# Aux_Power.net
KiCad netlist of a schematic drawn in Altium Designer
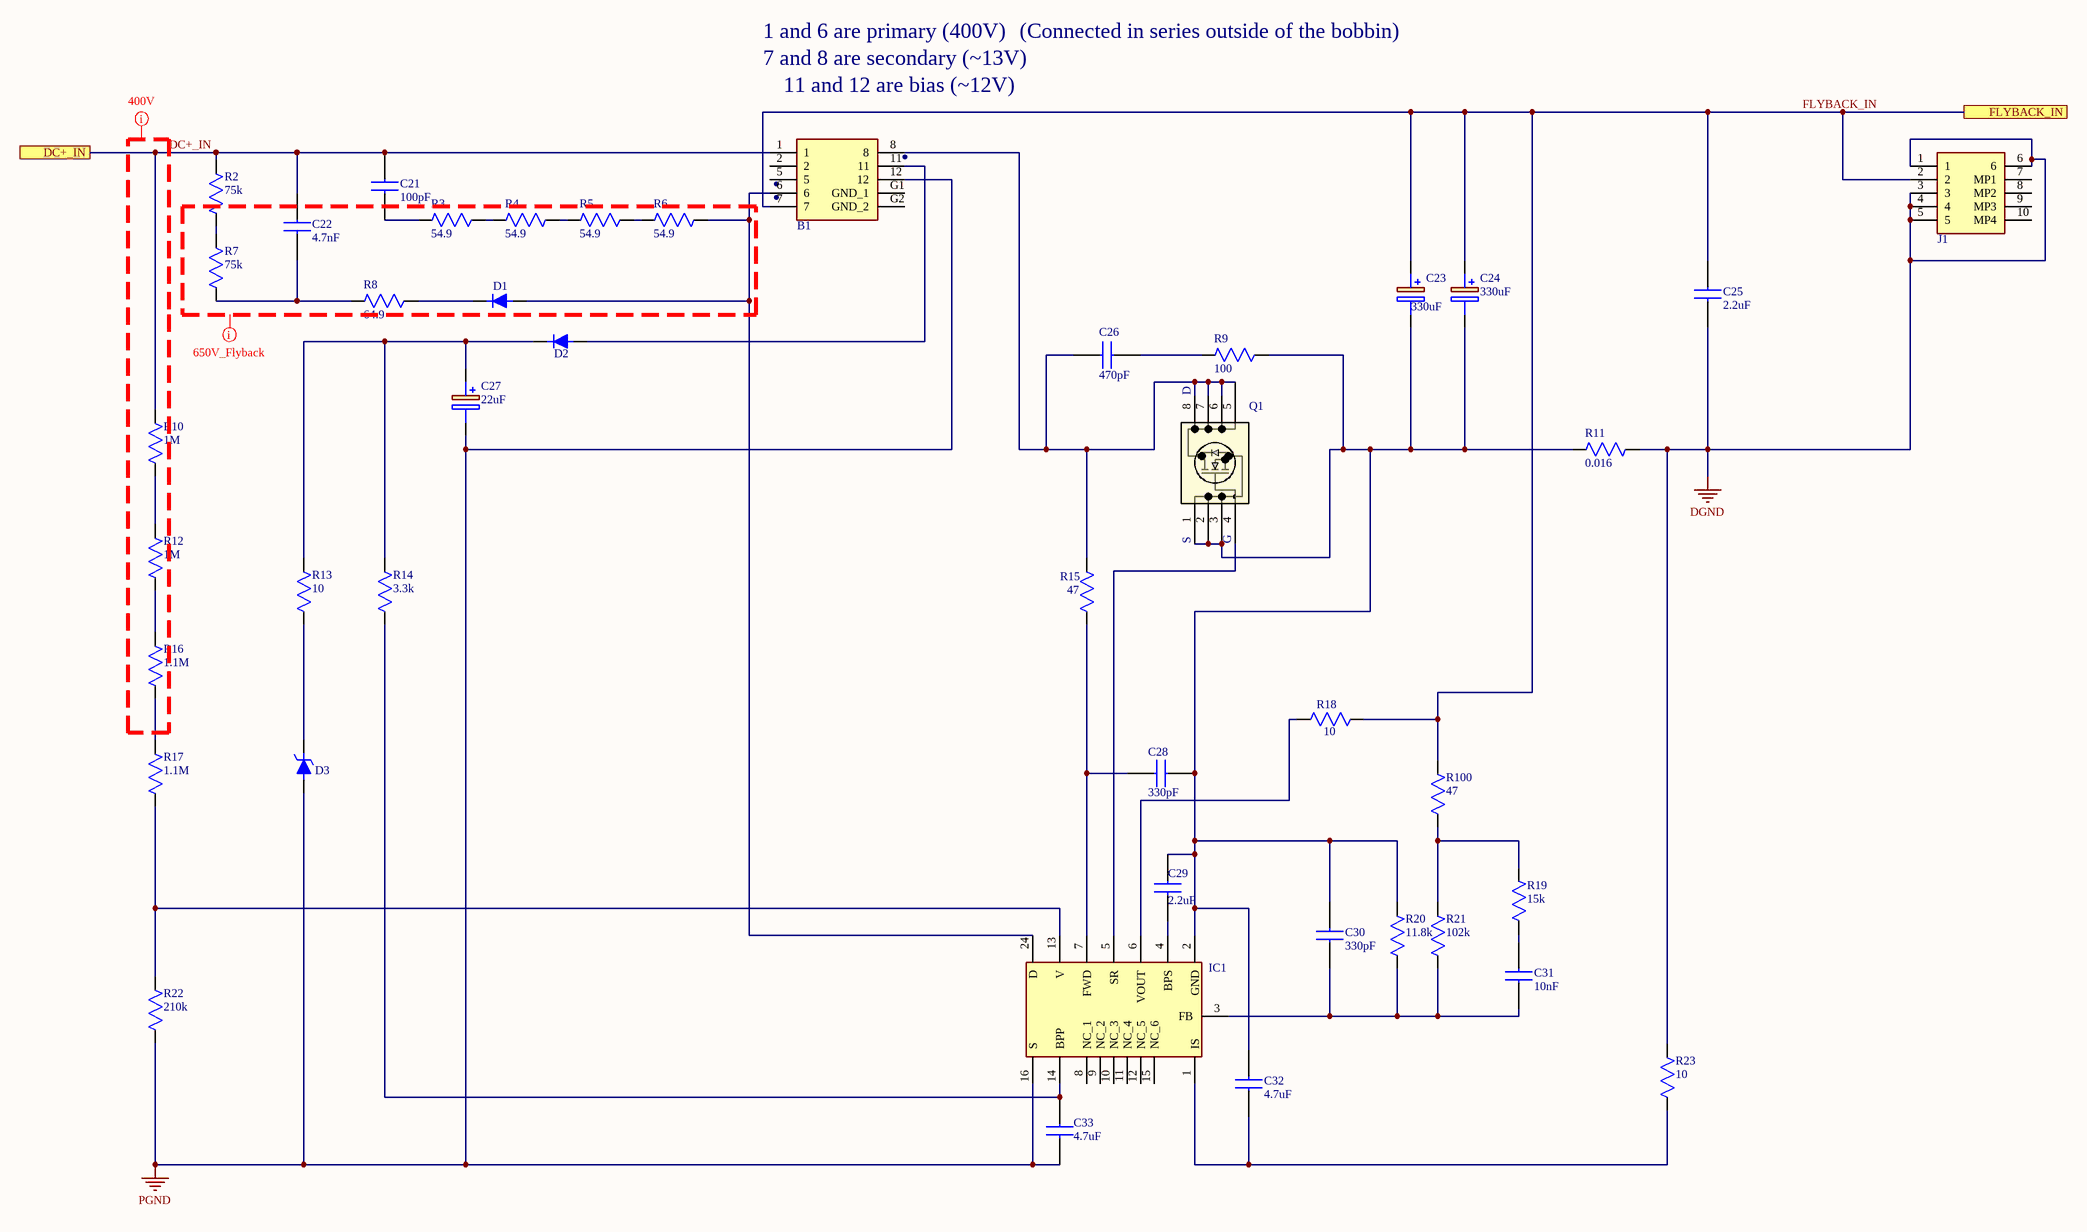
[diagram p0: Aux_Power.SchDoc]

(export (version "E")
  (design (tool "Eeschema 10.0.6"))
  (components
    (comp (ref "B1")
      (value "B65812N1008D001")
      (footprint "B65812N1008D001 - duplicate")
      (description "BOBBIN COIL FORMER RM 8")
      (fields (field (name "MOUSER PART NUMBER") "871-B65812N1008D001"))
      (libsource (lib "AuxPower") (part "B65812N1008D001"))
    )
    (comp (ref "C21")
      (value "100pF")
      (footprint "Cap 0805")
      (description "CAP CER 100PF 1000V X7R 0805")
      (libsource (lib "AuxPower") (part "885342207015"))
    )
    (comp (ref "C22")
      (value "4.7nF")
      (footprint "Cap 0805")
      (description "CAP CER 4700PF 450V C0G 0805")
      (libsource (lib "AuxPower") (part "C2012C0G2W472J125AA"))
    )
    (comp (ref "C23")
      (value "330uF")
      (footprint "CAPPC6465X560N")
      (description "CAP TANT 330UF 20% 20V 3226")
      (libsource (lib "AuxPower") (part "597D337X0020H2T"))
    )
    (comp (ref "C24")
      (value "330uF")
      (footprint "CAPPC6465X560N")
      (description "CAP TANT 330UF 20% 20V 3226")
      (libsource (lib "AuxPower") (part "597D337X0020H2T"))
    )
    (comp (ref "C25")
      (value "2.2uF")
      (footprint "Cap 0805")
      (description "2.2 µF ±10% 25V Ceramic Capacitor X7R 0805 (2012 Metric)")
      (libsource (lib "AuxPower") (part "CL21B225KAFNFNE"))
    )
    (comp (ref "C26")
      (value "470pF")
      (footprint "Cap 0805")
      (description "CAP CER 470PF 100V X7R 0805")
      (libsource (lib "AuxPower") (part "885012207114"))
    )
    (comp (ref "C27")
      (value "22uF")
      (footprint "CAP_195D_R_VIS")
      (description "CAP TANT 22UF 10% 35V 2824")
      (libsource (lib "AuxPower") (part "195D226X9035R2T"))
    )
    (comp (ref "C28")
      (value "330pF")
      (footprint "Cap 0805")
      (description "330 pF ±5% 250V Ceramic Capacitor C0G, NP0 0805 (2012 Metric)")
      (libsource (lib "AuxPower") (part "GCM21A5C2E331JX01D"))
    )
    (comp (ref "C29")
      (value "2.2uF")
      (footprint "Cap 0805")
      (description "2.2 µF ±10% 25V Ceramic Capacitor X7R 0805 (2012 Metric)")
      (libsource (lib "AuxPower") (part "CL21B225KAFNFNE"))
    )
    (comp (ref "C30")
      (value "330pF")
      (footprint "Cap 0805")
      (description "330 pF ±10% 50V Ceramic Capacitor X7R 0805 (2012 Metric)")
      (libsource (lib "AuxPower") (part "CC0805KRX7R9BB331"))
    )
    (comp (ref "C31")
      (value "10nF")
      (footprint "Cap 0805")
      (description "CAP CER 10000PF 25V X7R 0805")
      (libsource (lib "AuxPower") (part "CC0805KRX7R8BB103"))
    )
    (comp (ref "C32")
      (value "4.7uF")
      (footprint "Cap 0805")
      (description "4.7 µF ±10% 10V Ceramic Capacitor X7R 0805 (2012 Metric)")
      (libsource (lib "AuxPower") (part "LMK212B7475KGHT"))
    )
    (comp (ref "C33")
      (value "4.7uF")
      (footprint "Cap 0805")
      (description "4.7 µF ±10% 16V Ceramic Capacitor X7R 0805 (2012 Metric)")
      (libsource (lib "AuxPower") (part "CL21B475KOFNNNE"))
    )
    (comp (ref "D1")
      (value "637-S2T")
      (footprint "DO-214AA_SMB")
      (description "Diotec Semiconductor              Rectifiers Diode, SMB, 1300V, 2A")
      (fields
        (field (name "MANUFACTURER_PART_NUMBER") "UFM13PL-TP")
        (field (name "MOUSER PART NUMBER") "833-UFM13PL-TP")
      )
      (libsource (lib "AuxPower") (part "637-S2T"))
    )
    (comp (ref "D2")
      (value "BAV21WS-7-F")
      (footprint "SOD2513X120N")
      (description "DIODE STANDARD 200V 200MA SOD323")
      (fields
        (field (name "MANUFACTURER_PART_NUMBER") "UFM13PL-TP")
        (field (name "MOUSER PART NUMBER") "833-UFM13PL-TP")
      )
      (libsource (lib "AuxPower") (part "BAV21WS-7-F"))
    )
    (comp (ref "D3")
      (value "MMSZ5247BT1G")
      (footprint "SOD3716X135N")
      (description "Zener Diode 17 V 500 mW ±5% Surface Mount SOD-123")
      (fields
        (field (name "MANUFACTURER_PART_NUMBER") "UFM13PL-TP")
        (field (name "MOUSER PART NUMBER") "833-UFM13PL-TP")
      )
      (libsource (lib "AuxPower") (part "MMSZ5247BT1G"))
    )
    (comp (ref "IC1")
      (value "Flyback converter IC")
      (footprint "INN3694CH606TL")
      (description "Converter Offline Flyback, Secondary Side SR Topology 100kHz InSOP-24D")
      (fields
        (field (name "MANUFACTURER_PART_NUMBER") "INN3694C-H606-TL")
        (field (name "MOUSER PART NUMBER") "869-INN3694C-H606-TL")
      )
      (libsource (lib "AuxPower") (part "INN3694C-H606-TL"))
    )
    (comp (ref "J1")
      (value "0527450696")
      (footprint "0527450696")
      (description "CONN FFC FPC TOP 6POS 0.5MM R/A")
      (libsource (lib "AuxPower") (part "0527450696"))
    )
    (comp (ref "Q1")
      (value "AON6250")
      (footprint "AON6250")
      (description "MOSFET N-CH 150V 13.5A/52A 8DFN")
      (libsource (lib "AuxPower") (part "AON6250"))
    )
    (comp (ref "R2")
      (value "75k")
      (footprint "Resistor 0805")
      (description "RES 75K OHM 1% 1/8W 0805")
      (libsource (lib "AuxPower") (part "RMCF0805FT75K0"))
    )
    (comp (ref "R3")
      (value "54.9")
      (footprint "RESISTOR 1210")
      (description "RES 54.9 OHM 1% 1/2W 1210")
      (libsource (lib "AuxPower") (part "RMCF1210FT54R9"))
    )
    (comp (ref "R4")
      (value "54.9")
      (footprint "RESISTOR 1210")
      (description "RES 54.9 OHM 1% 1/2W 1210")
      (libsource (lib "AuxPower") (part "RMCF1210FT54R9"))
    )
    (comp (ref "R5")
      (value "54.9")
      (footprint "RESISTOR 1210")
      (description "RES 54.9 OHM 1% 1/2W 1210")
      (libsource (lib "AuxPower") (part "RMCF1210FT54R9"))
    )
    (comp (ref "R6")
      (value "54.9")
      (footprint "RESISTOR 1210")
      (description "RES 54.9 OHM 1% 1/2W 1210")
      (libsource (lib "AuxPower") (part "RMCF1210FT54R9"))
    )
    (comp (ref "R7")
      (value "75k")
      (footprint "Resistor 0805")
      (description "RES 75K OHM 1% 1/8W 0805")
      (libsource (lib "AuxPower") (part "RMCF0805FT75K0"))
    )
    (comp (ref "R8")
      (value "64.9")
      (footprint "RESISTOR 2512")
      (description "RES 64.9 OHM 1% 1W 2512")
      (libsource (lib "AuxPower") (part "RMCF2512FT64R9"))
    )
    (comp (ref "R9")
      (value "100")
      (footprint "Resistor 1206")
      (description "RES 100 OHM 1% 1/4W 1206")
      (libsource (lib "AuxPower") (part "RMCF1206FG100R"))
    )
    (comp (ref "R10")
      (value "1M")
      (footprint "Resistor 0805")
      (description "RES SMD 1M OHM 0.1% 1/8W 0805")
      (libsource (lib "AuxPower") (part "RG2012P-105-B-T5"))
    )
    (comp (ref "R11")
      (value "0.016")
      (footprint "Resistor 1206")
      (description "RES 0.016 OHM 1% 1/4W 1206")
      (libsource (lib "AuxPower") (part "RL1206FR-070R016L"))
    )
    (comp (ref "R12")
      (value "1M")
      (footprint "Resistor 0805")
      (description "RES SMD 1M OHM 0.1% 1/8W 0805")
      (libsource (lib "AuxPower") (part "RG2012P-105-B-T5"))
    )
    (comp (ref "R13")
      (value "10")
      (footprint "Resistor 0805")
      (description "RES 10 OHM 1% 1/10W 0805")
      (libsource (lib "AuxPower") (part "CR0805-10W-10R0FT"))
    )
    (comp (ref "R14")
      (value "3.3k")
      (footprint "Resistor 0805")
      (description "RES 3.3K OHM 1% 1/8W 0805")
      (libsource (lib "AuxPower") (part "RMCF0805FT3K30"))
    )
    (comp (ref "R15")
      (value "47")
      (footprint "Resistor 0805")
      (description "RES 47 OHM 1% 1/4W 0805")
      (libsource (lib "AuxPower") (part "RK73H2ATTD47R0F"))
    )
    (comp (ref "R16")
      (value "1.1M")
      (footprint "Resistor 0805")
      (description "RES SMD 1.1M OHM 0.1% 1/10W 0805")
      (libsource (lib "AuxPower") (part "CPF0805B1M1E1"))
    )
    (comp (ref "R17")
      (value "1.1M")
      (footprint "Resistor 0805")
      (description "RES SMD 1.1M OHM 0.1% 1/10W 0805")
      (libsource (lib "AuxPower") (part "CPF0805B1M1E1"))
    )
    (comp (ref "R18")
      (value "10")
      (footprint "Resistor 0805")
      (description "RES 10 OHM 1% 1/10W 0805")
      (libsource (lib "AuxPower") (part "CR0805-10W-10R0FT"))
    )
    (comp (ref "R19")
      (value "15k")
      (footprint "Resistor 0805")
      (description "CHIP RESISTOR,0805,1/10W, 15K,1%")
      (libsource (lib "AuxPower") (part "CR0805-10W-1502FT-CT"))
    )
    (comp (ref "R20")
      (value "11.8k")
      (footprint "Resistor 0603")
      (description "RES SMD 11.8K OHM 1% 1/10W 0603")
      (libsource (lib "AuxPower") (part "ERJ-3EKF1182V"))
    )
    (comp (ref "R21")
      (value "102k")
      (footprint "Resistor 0603")
      (description "RES SMD 102K OHM 1% 1/10W 0603")
      (libsource (lib "AuxPower") (part "ERJ-3EKF1023V"))
    )
    (comp (ref "R22")
      (value "210k")
      (footprint "Resistor 0805")
      (description "RES SMD 210K OHM 0.1% 1/8W 0805")
      (libsource (lib "AuxPower") (part "ERA-6AEB2103V"))
    )
    (comp (ref "R23")
      (value "10")
      (footprint "Resistor 0805")
      (description "RES SMD 10 OHM 1% 1/8W 0805")
      (libsource (lib "AuxPower") (part "ERJ-6ENF10R0V"))
    )
    (comp (ref "R100")
      (value "47")
      (footprint "Resistor 0805")
      (description "RES 47 OHM 1% 1/4W 0805")
      (libsource (lib "AuxPower") (part "RK73H2ATTD47R0F"))
    )
  )
  (nets
    (net (code "1") (name "/DC+_IN") (class "Default")
      (node (ref "B1") (pin "1") (pinfunction "1_1") (pintype "passive"))
      (node (ref "C21") (pin "2") (pinfunction "2_2") (pintype "passive"))
      (node (ref "C22") (pin "2") (pinfunction "2_2") (pintype "passive"))
      (node (ref "R10") (pin "2") (pinfunction "2_2") (pintype "passive"))
      (node (ref "R2") (pin "2") (pinfunction "2_2") (pintype "passive"))
    )
    (net (code "2") (name "/FLYBACK_IN") (class "Default")
      (node (ref "B1") (pin "7") (pinfunction "7_7") (pintype "passive"))
      (node (ref "C23") (pin "1") (pinfunction "+_1") (pintype "passive"))
      (node (ref "C24") (pin "1") (pinfunction "+_1") (pintype "passive"))
      (node (ref "C25") (pin "2") (pinfunction "2_2") (pintype "passive"))
      (node (ref "J1") (pin "2") (pinfunction "2_2") (pintype "passive"))
      (node (ref "R100") (pin "2") (pinfunction "2_2") (pintype "passive"))
      (node (ref "R18") (pin "1") (pinfunction "1_1") (pintype "passive"))
    )
    (net (code "3") (name "DGND") (class "Default")
      (node (ref "C25") (pin "1") (pinfunction "1_1") (pintype "passive"))
      (node (ref "J1") (pin "1") (pinfunction "1_1") (pintype "passive"))
      (node (ref "J1") (pin "3") (pinfunction "3_3") (pintype "passive"))
      (node (ref "J1") (pin "4") (pinfunction "4_4") (pintype "passive"))
      (node (ref "J1") (pin "5") (pinfunction "5_5") (pintype "passive"))
      (node (ref "J1") (pin "6") (pinfunction "6_6") (pintype "passive"))
      (node (ref "R11") (pin "2") (pinfunction "2_2") (pintype "passive"))
      (node (ref "R23") (pin "2") (pinfunction "2_2") (pintype "passive"))
    )
    (net (code "4") (name "Net-(B1-Pad8)") (class "Default")
      (node (ref "B1") (pin "8") (pinfunction "8_8") (pintype "passive"))
      (node (ref "C26") (pin "1") (pinfunction "1_1") (pintype "passive"))
      (node (ref "Q1") (pin "5") (pinfunction "5_5") (pintype "passive"))
      (node (ref "Q1") (pin "6") (pinfunction "6_6") (pintype "passive"))
      (node (ref "Q1") (pin "7") (pinfunction "7_7") (pintype "passive"))
      (node (ref "Q1") (pin "8") (pinfunction "8_8") (pintype "passive"))
      (node (ref "R15") (pin "2") (pinfunction "2_2") (pintype "passive"))
    )
    (net (code "5") (name "Net-(B1-Pad11)") (class "Default")
      (node (ref "B1") (pin "11") (pinfunction "11_11") (pintype "passive"))
      (node (ref "D2") (pin "1") (pinfunction "1_1") (pintype "passive"))
    )
    (net (code "6") (name "Net-(C21-Pad1)") (class "Default")
      (node (ref "C21") (pin "1") (pinfunction "1_1") (pintype "passive"))
      (node (ref "R3") (pin "1") (pinfunction "1_1") (pintype "passive"))
    )
    (net (code "7") (name "Net-(C22-Pad1)") (class "Default")
      (node (ref "C22") (pin "1") (pinfunction "1_1") (pintype "passive"))
      (node (ref "R7") (pin "1") (pinfunction "1_1") (pintype "passive"))
      (node (ref "R8") (pin "1") (pinfunction "1_1") (pintype "passive"))
    )
    (net (code "8") (name "Net-(C23--)") (class "Default")
      (node (ref "C23") (pin "2") (pinfunction "-_2") (pintype "passive"))
      (node (ref "C24") (pin "2") (pinfunction "-_2") (pintype "passive"))
      (node (ref "C28") (pin "2") (pinfunction "2_2") (pintype "passive"))
      (node (ref "C29") (pin "2") (pinfunction "2_2") (pintype "passive"))
      (node (ref "C30") (pin "1") (pinfunction "1_1") (pintype "passive"))
      (node (ref "C32") (pin "1") (pinfunction "1_1") (pintype "passive"))
      (node (ref "IC1") (pin "2") (pinfunction "GND_2") (pintype "passive"))
      (node (ref "Q1") (pin "1") (pinfunction "1_1") (pintype "passive"))
      (node (ref "Q1") (pin "2") (pinfunction "2_2") (pintype "passive"))
      (node (ref "Q1") (pin "3") (pinfunction "3_3") (pintype "passive"))
      (node (ref "R11") (pin "1") (pinfunction "1_1") (pintype "passive"))
      (node (ref "R20") (pin "2") (pinfunction "2_2") (pintype "passive"))
      (node (ref "R9") (pin "2") (pinfunction "2_2") (pintype "passive"))
    )
    (net (code "9") (name "Net-(C26-Pad2)") (class "Default")
      (node (ref "C26") (pin "2") (pinfunction "2_2") (pintype "passive"))
      (node (ref "R9") (pin "1") (pinfunction "1_1") (pintype "passive"))
    )
    (net (code "10") (name "Net-(C27-+)") (class "Default")
      (node (ref "C27") (pin "1") (pinfunction "+_1") (pintype "passive"))
      (node (ref "D2") (pin "2") (pinfunction "2_2") (pintype "passive"))
      (node (ref "R13") (pin "2") (pinfunction "2_2") (pintype "passive"))
      (node (ref "R14") (pin "2") (pinfunction "2_2") (pintype "passive"))
    )
    (net (code "11") (name "Net-(C31-Pad1)") (class "Default")
      (node (ref "C31") (pin "1") (pinfunction "1_1") (pintype "passive"))
      (node (ref "R19") (pin "2") (pinfunction "2_2") (pintype "passive"))
    )
    (net (code "12") (name "Net-(D1-Pad2)") (class "Default")
      (node (ref "D1") (pin "2") (pinfunction "2_2") (pintype "passive"))
      (node (ref "R8") (pin "2") (pinfunction "2_2") (pintype "passive"))
    )
    (net (code "13") (name "Net-(D3-Pad2)") (class "Default")
      (node (ref "D3") (pin "2") (pinfunction "2_2") (pintype "passive"))
      (node (ref "R13") (pin "1") (pinfunction "1_1") (pintype "passive"))
    )
    (net (code "14") (name "Net-(IC1-BPP)") (class "Default")
      (node (ref "C33") (pin "2") (pinfunction "2_2") (pintype "passive"))
      (node (ref "IC1") (pin "14") (pinfunction "BPP_14") (pintype "passive"))
      (node (ref "R14") (pin "1") (pinfunction "1_1") (pintype "passive"))
    )
    (net (code "15") (name "Net-(IC1-BPS)") (class "Default")
      (node (ref "C29") (pin "1") (pinfunction "1_1") (pintype "passive"))
      (node (ref "IC1") (pin "4") (pinfunction "BPS_4") (pintype "passive"))
    )
    (net (code "16") (name "Net-(IC1-D)") (class "Default")
      (node (ref "B1") (pin "6") (pinfunction "6_6") (pintype "passive"))
      (node (ref "D1") (pin "1") (pinfunction "1_1") (pintype "passive"))
      (node (ref "IC1") (pin "24") (pinfunction "D_24") (pintype "passive"))
      (node (ref "R6") (pin "2") (pinfunction "2_2") (pintype "passive"))
    )
    (net (code "17") (name "Net-(IC1-FB)") (class "Default")
      (node (ref "C30") (pin "2") (pinfunction "2_2") (pintype "passive"))
      (node (ref "C31") (pin "2") (pinfunction "2_2") (pintype "passive"))
      (node (ref "IC1") (pin "3") (pinfunction "FB_3") (pintype "passive"))
      (node (ref "R20") (pin "1") (pinfunction "1_1") (pintype "passive"))
      (node (ref "R21") (pin "1") (pinfunction "1_1") (pintype "passive"))
    )
    (net (code "18") (name "Net-(IC1-FWD)") (class "Default")
      (node (ref "C28") (pin "1") (pinfunction "1_1") (pintype "passive"))
      (node (ref "IC1") (pin "7") (pinfunction "FWD_7") (pintype "passive"))
      (node (ref "R15") (pin "1") (pinfunction "1_1") (pintype "passive"))
    )
    (net (code "19") (name "Net-(IC1-IS)") (class "Default")
      (node (ref "C32") (pin "2") (pinfunction "2_2") (pintype "passive"))
      (node (ref "IC1") (pin "1") (pinfunction "IS_1") (pintype "passive"))
      (node (ref "R23") (pin "1") (pinfunction "1_1") (pintype "passive"))
    )
    (net (code "20") (name "Net-(IC1-SR)") (class "Default")
      (node (ref "IC1") (pin "5") (pinfunction "SR_5") (pintype "passive"))
      (node (ref "Q1") (pin "4") (pinfunction "4_4") (pintype "passive"))
    )
    (net (code "21") (name "Net-(IC1-V)") (class "Default")
      (node (ref "IC1") (pin "13") (pinfunction "V_13") (pintype "passive"))
      (node (ref "R17") (pin "1") (pinfunction "1_1") (pintype "passive"))
      (node (ref "R22") (pin "2") (pinfunction "2_2") (pintype "passive"))
    )
    (net (code "22") (name "Net-(IC1-VOUT)") (class "Default")
      (node (ref "IC1") (pin "6") (pinfunction "VOUT_6") (pintype "passive"))
      (node (ref "R18") (pin "2") (pinfunction "2_2") (pintype "passive"))
    )
    (net (code "23") (name "Net-(R2-Pad1)") (class "Default")
      (node (ref "R2") (pin "1") (pinfunction "1_1") (pintype "passive"))
      (node (ref "R7") (pin "2") (pinfunction "2_2") (pintype "passive"))
    )
    (net (code "24") (name "Net-(R3-Pad2)") (class "Default")
      (node (ref "R3") (pin "2") (pinfunction "2_2") (pintype "passive"))
      (node (ref "R4") (pin "1") (pinfunction "1_1") (pintype "passive"))
    )
    (net (code "25") (name "Net-(R4-Pad2)") (class "Default")
      (node (ref "R4") (pin "2") (pinfunction "2_2") (pintype "passive"))
      (node (ref "R5") (pin "1") (pinfunction "1_1") (pintype "passive"))
    )
    (net (code "26") (name "Net-(R5-Pad2)") (class "Default")
      (node (ref "R5") (pin "2") (pinfunction "2_2") (pintype "passive"))
      (node (ref "R6") (pin "1") (pinfunction "1_1") (pintype "passive"))
    )
    (net (code "27") (name "Net-(R10-Pad1)") (class "Default")
      (node (ref "R10") (pin "1") (pinfunction "1_1") (pintype "passive"))
      (node (ref "R12") (pin "2") (pinfunction "2_2") (pintype "passive"))
    )
    (net (code "28") (name "Net-(R12-Pad1)") (class "Default")
      (node (ref "R12") (pin "1") (pinfunction "1_1") (pintype "passive"))
      (node (ref "R16") (pin "2") (pinfunction "2_2") (pintype "passive"))
    )
    (net (code "29") (name "Net-(R16-Pad1)") (class "Default")
      (node (ref "R16") (pin "1") (pinfunction "1_1") (pintype "passive"))
      (node (ref "R17") (pin "2") (pinfunction "2_2") (pintype "passive"))
    )
    (net (code "30") (name "Net-(R100-Pad1)") (class "Default")
      (node (ref "R100") (pin "1") (pinfunction "1_1") (pintype "passive"))
      (node (ref "R19") (pin "1") (pinfunction "1_1") (pintype "passive"))
      (node (ref "R21") (pin "2") (pinfunction "2_2") (pintype "passive"))
    )
    (net (code "31") (name "PGND") (class "Default")
      (node (ref "B1") (pin "12") (pinfunction "12_12") (pintype "passive"))
      (node (ref "C27") (pin "2") (pinfunction "-_2") (pintype "passive"))
      (node (ref "C33") (pin "1") (pinfunction "1_1") (pintype "passive"))
      (node (ref "D3") (pin "1") (pinfunction "1_1") (pintype "passive"))
      (node (ref "IC1") (pin "16") (pinfunction "S_16") (pintype "passive"))
      (node (ref "R22") (pin "1") (pinfunction "1_1") (pintype "passive"))
    )
    (net (code "32") (name "unconnected-(B1-GND_1-PadG1)") (class "Default")
      (node (ref "B1") (pin "G1") (pinfunction "GND_1_G1") (pintype "passive"))
    )
    (net (code "33") (name "unconnected-(B1-GND_2-PadG2)") (class "Default")
      (node (ref "B1") (pin "G2") (pinfunction "GND_2_G2") (pintype "passive"))
    )
    (net (code "34") (name "unconnected-(B1-Pad2)") (class "Default")
      (node (ref "B1") (pin "2") (pinfunction "2_2") (pintype "passive"))
    )
    (net (code "35") (name "unconnected-(B1-Pad5)") (class "Default")
      (node (ref "B1") (pin "5") (pinfunction "5_5") (pintype "passive"))
    )
    (net (code "36") (name "unconnected-(IC1-NC_1-Pad8)") (class "Default")
      (node (ref "IC1") (pin "8") (pinfunction "NC_1_8") (pintype "passive"))
    )
    (net (code "37") (name "unconnected-(IC1-NC_2-Pad9)") (class "Default")
      (node (ref "IC1") (pin "9") (pinfunction "NC_2_9") (pintype "passive"))
    )
    (net (code "38") (name "unconnected-(IC1-NC_3-Pad10)") (class "Default")
      (node (ref "IC1") (pin "10") (pinfunction "NC_3_10") (pintype "passive"))
    )
    (net (code "39") (name "unconnected-(IC1-NC_4-Pad11)") (class "Default")
      (node (ref "IC1") (pin "11") (pinfunction "NC_4_11") (pintype "passive"))
    )
    (net (code "40") (name "unconnected-(IC1-NC_5-Pad12)") (class "Default")
      (node (ref "IC1") (pin "12") (pinfunction "NC_5_12") (pintype "passive"))
    )
    (net (code "41") (name "unconnected-(IC1-NC_6-Pad15)") (class "Default")
      (node (ref "IC1") (pin "15") (pinfunction "NC_6_15") (pintype "passive"))
    )
    (net (code "42") (name "unconnected-(J1-MP1-Pad7)") (class "Default")
      (node (ref "J1") (pin "7") (pinfunction "MP1_7") (pintype "passive"))
    )
    (net (code "43") (name "unconnected-(J1-MP2-Pad8)") (class "Default")
      (node (ref "J1") (pin "8") (pinfunction "MP2_8") (pintype "passive"))
    )
    (net (code "44") (name "unconnected-(J1-MP3-Pad9)") (class "Default")
      (node (ref "J1") (pin "9") (pinfunction "MP3_9") (pintype "passive"))
    )
    (net (code "45") (name "unconnected-(J1-MP4-Pad10)") (class "Default")
      (node (ref "J1") (pin "10") (pinfunction "MP4_10") (pintype "passive"))
    )
  )
)
